# muxi.net
KiCad netlist of a schematic drawn in EAGLE
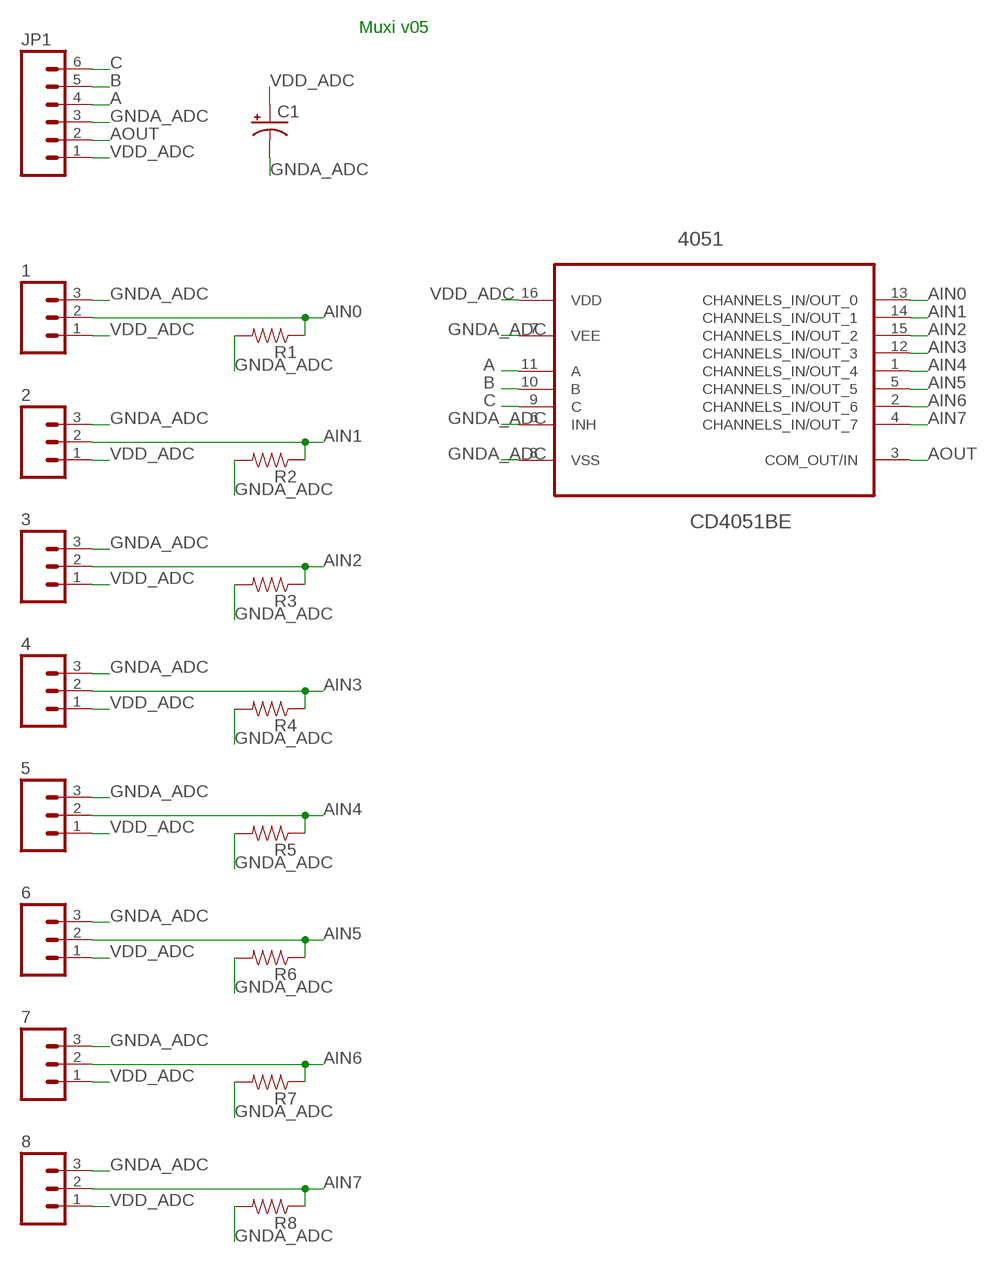
[diagram p0: schematic, sheet 1]

(export (version "E")
  (design (tool "Eeschema 10.0.6"))
  (components
    (comp (ref "1")
      (value "M03PTH")
      (footprint "eagle-import:1X03")
      (libsource (lib "eagle-import") (part "M03PTH"))
    )
    (comp (ref "2")
      (value "M03PTH")
      (footprint "eagle-import:1X03")
      (libsource (lib "eagle-import") (part "M03PTH"))
    )
    (comp (ref "3")
      (value "M03PTH")
      (footprint "eagle-import:1X03")
      (libsource (lib "eagle-import") (part "M03PTH"))
    )
    (comp (ref "4")
      (value "M03PTH")
      (footprint "eagle-import:1X03")
      (libsource (lib "eagle-import") (part "M03PTH"))
    )
    (comp (ref "5")
      (value "M03PTH")
      (footprint "eagle-import:1X03")
      (libsource (lib "eagle-import") (part "M03PTH"))
    )
    (comp (ref "6")
      (value "M03PTH")
      (footprint "eagle-import:1X03")
      (libsource (lib "eagle-import") (part "M03PTH"))
    )
    (comp (ref "7")
      (value "M03PTH")
      (footprint "eagle-import:1X03")
      (libsource (lib "eagle-import") (part "M03PTH"))
    )
    (comp (ref "8")
      (value "M03PTH")
      (footprint "eagle-import:1X03")
      (libsource (lib "eagle-import") (part "M03PTH"))
    )
    (comp (ref "4051")
      (value "CD4051BE")
      (footprint "eagle-import:DIP254P762X508-16")
      (libsource (lib "eagle-import") (part "CD4051BE"))
    )
    (comp (ref "C1")
      (value "CAP_POLPTH2")
      (footprint "eagle-import:CPOL-RADIAL-10UF-25V")
      (libsource (lib "eagle-import") (part "CAP_POLPTH2"))
    )
    (comp (ref "JP1")
      (value "M06NO_SILK")
      (footprint "eagle-import:1X06_NO_SILK")
      (libsource (lib "eagle-import") (part "M06NO_SILK"))
    )
    (comp (ref "R1")
      (value "RESISTORAXIAL-0.3")
      (footprint "eagle-import:AXIAL-0.3")
      (libsource (lib "eagle-import") (part "RESISTORAXIAL-0.3"))
    )
    (comp (ref "R2")
      (value "RESISTORAXIAL-0.3")
      (footprint "eagle-import:AXIAL-0.3")
      (libsource (lib "eagle-import") (part "RESISTORAXIAL-0.3"))
    )
    (comp (ref "R3")
      (value "RESISTORAXIAL-0.3")
      (footprint "eagle-import:AXIAL-0.3")
      (libsource (lib "eagle-import") (part "RESISTORAXIAL-0.3"))
    )
    (comp (ref "R4")
      (value "RESISTORAXIAL-0.3")
      (footprint "eagle-import:AXIAL-0.3")
      (libsource (lib "eagle-import") (part "RESISTORAXIAL-0.3"))
    )
    (comp (ref "R5")
      (value "RESISTORAXIAL-0.3")
      (footprint "eagle-import:AXIAL-0.3")
      (libsource (lib "eagle-import") (part "RESISTORAXIAL-0.3"))
    )
    (comp (ref "R6")
      (value "RESISTORAXIAL-0.3")
      (footprint "eagle-import:AXIAL-0.3")
      (libsource (lib "eagle-import") (part "RESISTORAXIAL-0.3"))
    )
    (comp (ref "R7")
      (value "RESISTORAXIAL-0.3")
      (footprint "eagle-import:AXIAL-0.3")
      (libsource (lib "eagle-import") (part "RESISTORAXIAL-0.3"))
    )
    (comp (ref "R8")
      (value "RESISTORAXIAL-0.3")
      (footprint "eagle-import:AXIAL-0.3")
      (libsource (lib "eagle-import") (part "RESISTORAXIAL-0.3"))
    )
  )
  (nets
    (net (code "1") (name "/A") (class "Default")
      (node (ref "4051") (pin "11") (pinfunction "A_11") (pintype "input"))
      (node (ref "JP1") (pin "4") (pinfunction "4_4") (pintype "passive"))
    )
    (net (code "2") (name "/AIN0") (class "Default")
      (node (ref "1") (pin "2") (pinfunction "2_2") (pintype "passive"))
      (node (ref "4051") (pin "13") (pinfunction "CHANNELS_IN/OUT_0_13") (pintype "bidirectional"))
      (node (ref "R1") (pin "P$1") (pinfunction "1_P$1") (pintype "passive"))
    )
    (net (code "3") (name "/AIN1") (class "Default")
      (node (ref "2") (pin "2") (pinfunction "2_2") (pintype "passive"))
      (node (ref "4051") (pin "14") (pinfunction "CHANNELS_IN/OUT_1_14") (pintype "bidirectional"))
      (node (ref "R2") (pin "P$1") (pinfunction "1_P$1") (pintype "passive"))
    )
    (net (code "4") (name "/AIN2") (class "Default")
      (node (ref "3") (pin "2") (pinfunction "2_2") (pintype "passive"))
      (node (ref "4051") (pin "15") (pinfunction "CHANNELS_IN/OUT_2_15") (pintype "bidirectional"))
      (node (ref "R3") (pin "P$1") (pinfunction "1_P$1") (pintype "passive"))
    )
    (net (code "5") (name "/AIN3") (class "Default")
      (node (ref "4") (pin "2") (pinfunction "2_2") (pintype "passive"))
      (node (ref "4051") (pin "12") (pinfunction "CHANNELS_IN/OUT_3_12") (pintype "bidirectional"))
      (node (ref "R4") (pin "P$1") (pinfunction "1_P$1") (pintype "passive"))
    )
    (net (code "6") (name "/AIN4") (class "Default")
      (node (ref "4051") (pin "1") (pinfunction "CHANNELS_IN/OUT_4_1") (pintype "bidirectional"))
      (node (ref "5") (pin "2") (pinfunction "2_2") (pintype "passive"))
      (node (ref "R5") (pin "P$1") (pinfunction "1_P$1") (pintype "passive"))
    )
    (net (code "7") (name "/AIN5") (class "Default")
      (node (ref "4051") (pin "5") (pinfunction "CHANNELS_IN/OUT_5_5") (pintype "bidirectional"))
      (node (ref "6") (pin "2") (pinfunction "2_2") (pintype "passive"))
      (node (ref "R6") (pin "P$1") (pinfunction "1_P$1") (pintype "passive"))
    )
    (net (code "8") (name "/AIN6") (class "Default")
      (node (ref "4051") (pin "2") (pinfunction "CHANNELS_IN/OUT_6_2") (pintype "bidirectional"))
      (node (ref "7") (pin "2") (pinfunction "2_2") (pintype "passive"))
      (node (ref "R7") (pin "P$1") (pinfunction "1_P$1") (pintype "passive"))
    )
    (net (code "9") (name "/AIN7") (class "Default")
      (node (ref "4051") (pin "4") (pinfunction "CHANNELS_IN/OUT_7_4") (pintype "bidirectional"))
      (node (ref "8") (pin "2") (pinfunction "2_2") (pintype "passive"))
      (node (ref "R8") (pin "P$1") (pinfunction "1_P$1") (pintype "passive"))
    )
    (net (code "10") (name "/AOUT") (class "Default")
      (node (ref "4051") (pin "3") (pinfunction "COM_OUT/IN_3") (pintype "bidirectional"))
      (node (ref "JP1") (pin "2") (pinfunction "2_2") (pintype "passive"))
    )
    (net (code "11") (name "/B") (class "Default")
      (node (ref "4051") (pin "10") (pinfunction "B_10") (pintype "input"))
      (node (ref "JP1") (pin "5") (pinfunction "5_5") (pintype "passive"))
    )
    (net (code "12") (name "/C") (class "Default")
      (node (ref "4051") (pin "9") (pinfunction "C_9") (pintype "input"))
      (node (ref "JP1") (pin "6") (pinfunction "6_6") (pintype "passive"))
    )
    (net (code "13") (name "/GNDA_ADC") (class "Default")
      (node (ref "1") (pin "3") (pinfunction "3_3") (pintype "passive"))
      (node (ref "2") (pin "3") (pinfunction "3_3") (pintype "passive"))
      (node (ref "3") (pin "3") (pinfunction "3_3") (pintype "passive"))
      (node (ref "4") (pin "3") (pinfunction "3_3") (pintype "passive"))
      (node (ref "4051") (pin "6") (pinfunction "INH_6") (pintype "input"))
      (node (ref "4051") (pin "7") (pinfunction "VEE_7") (pintype "power_in"))
      (node (ref "4051") (pin "8") (pinfunction "VSS_8") (pintype "power_in"))
      (node (ref "5") (pin "3") (pinfunction "3_3") (pintype "passive"))
      (node (ref "6") (pin "3") (pinfunction "3_3") (pintype "passive"))
      (node (ref "7") (pin "3") (pinfunction "3_3") (pintype "passive"))
      (node (ref "8") (pin "3") (pinfunction "3_3") (pintype "passive"))
      (node (ref "C1") (pin "2") (pinfunction "-_2") (pintype "passive"))
      (node (ref "JP1") (pin "3") (pinfunction "3_3") (pintype "passive"))
      (node (ref "R1") (pin "P$2") (pinfunction "2_P$2") (pintype "passive"))
      (node (ref "R2") (pin "P$2") (pinfunction "2_P$2") (pintype "passive"))
      (node (ref "R3") (pin "P$2") (pinfunction "2_P$2") (pintype "passive"))
      (node (ref "R4") (pin "P$2") (pinfunction "2_P$2") (pintype "passive"))
      (node (ref "R5") (pin "P$2") (pinfunction "2_P$2") (pintype "passive"))
      (node (ref "R6") (pin "P$2") (pinfunction "2_P$2") (pintype "passive"))
      (node (ref "R7") (pin "P$2") (pinfunction "2_P$2") (pintype "passive"))
      (node (ref "R8") (pin "P$2") (pinfunction "2_P$2") (pintype "passive"))
    )
    (net (code "14") (name "/VDD_ADC") (class "Default")
      (node (ref "1") (pin "1") (pinfunction "1_1") (pintype "passive"))
      (node (ref "2") (pin "1") (pinfunction "1_1") (pintype "passive"))
      (node (ref "3") (pin "1") (pinfunction "1_1") (pintype "passive"))
      (node (ref "4") (pin "1") (pinfunction "1_1") (pintype "passive"))
      (node (ref "4051") (pin "16") (pinfunction "VDD_16") (pintype "power_in"))
      (node (ref "5") (pin "1") (pinfunction "1_1") (pintype "passive"))
      (node (ref "6") (pin "1") (pinfunction "1_1") (pintype "passive"))
      (node (ref "7") (pin "1") (pinfunction "1_1") (pintype "passive"))
      (node (ref "8") (pin "1") (pinfunction "1_1") (pintype "passive"))
      (node (ref "C1") (pin "1") (pinfunction "+_1") (pintype "passive"))
      (node (ref "JP1") (pin "1") (pinfunction "1_1") (pintype "passive"))
    )
  )
)
